# ext_proto_M.net
KiCad netlist of a schematic drawn in EAGLE
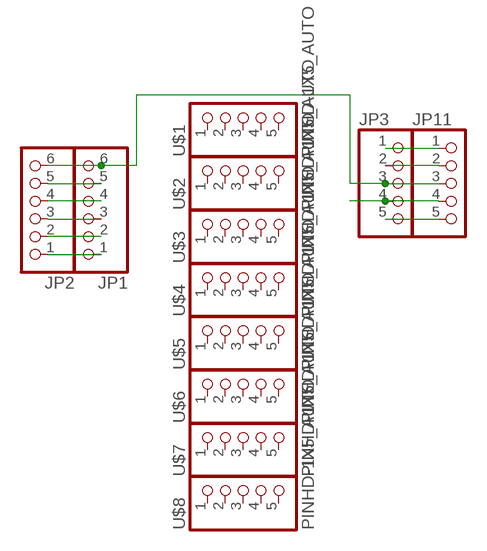
[diagram p0: schematic, sheet 1]

(export (version "E")
  (design (tool "Eeschema 10.0.6"))
  (components
    (comp (ref "JP1")
      (value "PINHD-1X6")
      (footprint "eagle-import:1X06")
      (libsource (lib "eagle-import") (part "PINHD-1X6"))
    )
    (comp (ref "JP2")
      (value "PINHD-1X6")
      (footprint "eagle-import:1X06")
      (libsource (lib "eagle-import") (part "PINHD-1X6"))
    )
    (comp (ref "JP3")
      (value "PINHD-1X5")
      (footprint "eagle-import:1X05")
      (libsource (lib "eagle-import") (part "PINHD-1X5"))
    )
    (comp (ref "JP11")
      (value "PINHD-1X5")
      (footprint "eagle-import:1X05")
      (libsource (lib "eagle-import") (part "PINHD-1X5"))
    )
    (comp (ref "U$1")
      (value "PINHD-1X5_AUTO")
      (footprint "eagle-import:1X5_AUTO")
      (libsource (lib "eagle-import") (part "PINHD-1X5_AUTO"))
    )
    (comp (ref "U$2")
      (value "PINHD-1X5_AUTO")
      (footprint "eagle-import:1X5_AUTO")
      (libsource (lib "eagle-import") (part "PINHD-1X5_AUTO"))
    )
    (comp (ref "U$3")
      (value "PINHD-1X5_AUTO")
      (footprint "eagle-import:1X5_AUTO")
      (libsource (lib "eagle-import") (part "PINHD-1X5_AUTO"))
    )
    (comp (ref "U$4")
      (value "PINHD-1X5_AUTO")
      (footprint "eagle-import:1X5_AUTO")
      (libsource (lib "eagle-import") (part "PINHD-1X5_AUTO"))
    )
    (comp (ref "U$5")
      (value "PINHD-1X5_AUTO")
      (footprint "eagle-import:1X5_AUTO")
      (libsource (lib "eagle-import") (part "PINHD-1X5_AUTO"))
    )
    (comp (ref "U$6")
      (value "PINHD-1X5_AUTO")
      (footprint "eagle-import:1X5_AUTO")
      (libsource (lib "eagle-import") (part "PINHD-1X5_AUTO"))
    )
    (comp (ref "U$7")
      (value "PINHD-1X5_AUTO")
      (footprint "eagle-import:1X5_AUTO")
      (libsource (lib "eagle-import") (part "PINHD-1X5_AUTO"))
    )
    (comp (ref "U$8")
      (value "PINHD-1X5_AUTO")
      (footprint "eagle-import:1X5_AUTO")
      (libsource (lib "eagle-import") (part "PINHD-1X5_AUTO"))
    )
  )
  (nets
    (net (code "1") (name "Net-(JP1-Pad1)") (class "Default")
      (node (ref "JP1") (pin "1") (pinfunction "1_1") (pintype "passive"))
      (node (ref "JP2") (pin "1") (pinfunction "1_1") (pintype "passive"))
    )
    (net (code "2") (name "Net-(JP1-Pad2)") (class "Default")
      (node (ref "JP1") (pin "2") (pinfunction "2_2") (pintype "passive"))
      (node (ref "JP2") (pin "2") (pinfunction "2_2") (pintype "passive"))
    )
    (net (code "3") (name "Net-(JP1-Pad3)") (class "Default")
      (node (ref "JP1") (pin "3") (pinfunction "3_3") (pintype "passive"))
      (node (ref "JP2") (pin "3") (pinfunction "3_3") (pintype "passive"))
    )
    (net (code "4") (name "Net-(JP1-Pad4)") (class "Default")
      (node (ref "JP1") (pin "4") (pinfunction "4_4") (pintype "passive"))
      (node (ref "JP2") (pin "4") (pinfunction "4_4") (pintype "passive"))
    )
    (net (code "5") (name "Net-(JP1-Pad5)") (class "Default")
      (node (ref "JP1") (pin "5") (pinfunction "5_5") (pintype "passive"))
      (node (ref "JP2") (pin "5") (pinfunction "5_5") (pintype "passive"))
    )
    (net (code "6") (name "Net-(JP1-Pad6)") (class "Default")
      (node (ref "JP1") (pin "6") (pinfunction "6_6") (pintype "passive"))
      (node (ref "JP11") (pin "3") (pinfunction "3_3") (pintype "passive"))
      (node (ref "JP2") (pin "6") (pinfunction "6_6") (pintype "passive"))
      (node (ref "JP3") (pin "3") (pinfunction "3_3") (pintype "passive"))
    )
    (net (code "7") (name "Net-(JP11-Pad1)") (class "Default")
      (node (ref "JP11") (pin "1") (pinfunction "1_1") (pintype "passive"))
      (node (ref "JP3") (pin "1") (pinfunction "1_1") (pintype "passive"))
    )
    (net (code "8") (name "Net-(JP11-Pad2)") (class "Default")
      (node (ref "JP11") (pin "2") (pinfunction "2_2") (pintype "passive"))
      (node (ref "JP3") (pin "2") (pinfunction "2_2") (pintype "passive"))
    )
    (net (code "9") (name "Net-(JP11-Pad4)") (class "Default")
      (node (ref "JP11") (pin "4") (pinfunction "4_4") (pintype "passive"))
      (node (ref "JP3") (pin "4") (pinfunction "4_4") (pintype "passive"))
    )
    (net (code "10") (name "Net-(JP11-Pad5)") (class "Default")
      (node (ref "JP11") (pin "5") (pinfunction "5_5") (pintype "passive"))
      (node (ref "JP3") (pin "5") (pinfunction "5_5") (pintype "passive"))
    )
    (net (code "11") (name "unconnected-(U$1-Pad1)") (class "Default")
      (node (ref "U$1") (pin "1") (pinfunction "1_1") (pintype "passive"))
    )
    (net (code "12") (name "unconnected-(U$1-Pad2)") (class "Default")
      (node (ref "U$1") (pin "2") (pinfunction "2_2") (pintype "passive"))
    )
    (net (code "13") (name "unconnected-(U$1-Pad3)") (class "Default")
      (node (ref "U$1") (pin "3") (pinfunction "3_3") (pintype "passive"))
    )
    (net (code "14") (name "unconnected-(U$1-Pad4)") (class "Default")
      (node (ref "U$1") (pin "4") (pinfunction "4_4") (pintype "passive"))
    )
    (net (code "15") (name "unconnected-(U$1-Pad5)") (class "Default")
      (node (ref "U$1") (pin "5") (pinfunction "5_5") (pintype "passive"))
    )
    (net (code "16") (name "unconnected-(U$2-Pad1)") (class "Default")
      (node (ref "U$2") (pin "1") (pinfunction "1_1") (pintype "passive"))
    )
    (net (code "17") (name "unconnected-(U$2-Pad2)") (class "Default")
      (node (ref "U$2") (pin "2") (pinfunction "2_2") (pintype "passive"))
    )
    (net (code "18") (name "unconnected-(U$2-Pad3)") (class "Default")
      (node (ref "U$2") (pin "3") (pinfunction "3_3") (pintype "passive"))
    )
    (net (code "19") (name "unconnected-(U$2-Pad4)") (class "Default")
      (node (ref "U$2") (pin "4") (pinfunction "4_4") (pintype "passive"))
    )
    (net (code "20") (name "unconnected-(U$2-Pad5)") (class "Default")
      (node (ref "U$2") (pin "5") (pinfunction "5_5") (pintype "passive"))
    )
    (net (code "21") (name "unconnected-(U$3-Pad1)") (class "Default")
      (node (ref "U$3") (pin "1") (pinfunction "1_1") (pintype "passive"))
    )
    (net (code "22") (name "unconnected-(U$3-Pad2)") (class "Default")
      (node (ref "U$3") (pin "2") (pinfunction "2_2") (pintype "passive"))
    )
    (net (code "23") (name "unconnected-(U$3-Pad3)") (class "Default")
      (node (ref "U$3") (pin "3") (pinfunction "3_3") (pintype "passive"))
    )
    (net (code "24") (name "unconnected-(U$3-Pad4)") (class "Default")
      (node (ref "U$3") (pin "4") (pinfunction "4_4") (pintype "passive"))
    )
    (net (code "25") (name "unconnected-(U$3-Pad5)") (class "Default")
      (node (ref "U$3") (pin "5") (pinfunction "5_5") (pintype "passive"))
    )
    (net (code "26") (name "unconnected-(U$4-Pad1)") (class "Default")
      (node (ref "U$4") (pin "1") (pinfunction "1_1") (pintype "passive"))
    )
    (net (code "27") (name "unconnected-(U$4-Pad2)") (class "Default")
      (node (ref "U$4") (pin "2") (pinfunction "2_2") (pintype "passive"))
    )
    (net (code "28") (name "unconnected-(U$4-Pad3)") (class "Default")
      (node (ref "U$4") (pin "3") (pinfunction "3_3") (pintype "passive"))
    )
    (net (code "29") (name "unconnected-(U$4-Pad4)") (class "Default")
      (node (ref "U$4") (pin "4") (pinfunction "4_4") (pintype "passive"))
    )
    (net (code "30") (name "unconnected-(U$4-Pad5)") (class "Default")
      (node (ref "U$4") (pin "5") (pinfunction "5_5") (pintype "passive"))
    )
    (net (code "31") (name "unconnected-(U$5-Pad1)") (class "Default")
      (node (ref "U$5") (pin "1") (pinfunction "1_1") (pintype "passive"))
    )
    (net (code "32") (name "unconnected-(U$5-Pad2)") (class "Default")
      (node (ref "U$5") (pin "2") (pinfunction "2_2") (pintype "passive"))
    )
    (net (code "33") (name "unconnected-(U$5-Pad3)") (class "Default")
      (node (ref "U$5") (pin "3") (pinfunction "3_3") (pintype "passive"))
    )
    (net (code "34") (name "unconnected-(U$5-Pad4)") (class "Default")
      (node (ref "U$5") (pin "4") (pinfunction "4_4") (pintype "passive"))
    )
    (net (code "35") (name "unconnected-(U$5-Pad5)") (class "Default")
      (node (ref "U$5") (pin "5") (pinfunction "5_5") (pintype "passive"))
    )
    (net (code "36") (name "unconnected-(U$6-Pad1)") (class "Default")
      (node (ref "U$6") (pin "1") (pinfunction "1_1") (pintype "passive"))
    )
    (net (code "37") (name "unconnected-(U$6-Pad2)") (class "Default")
      (node (ref "U$6") (pin "2") (pinfunction "2_2") (pintype "passive"))
    )
    (net (code "38") (name "unconnected-(U$6-Pad3)") (class "Default")
      (node (ref "U$6") (pin "3") (pinfunction "3_3") (pintype "passive"))
    )
    (net (code "39") (name "unconnected-(U$6-Pad4)") (class "Default")
      (node (ref "U$6") (pin "4") (pinfunction "4_4") (pintype "passive"))
    )
    (net (code "40") (name "unconnected-(U$6-Pad5)") (class "Default")
      (node (ref "U$6") (pin "5") (pinfunction "5_5") (pintype "passive"))
    )
    (net (code "41") (name "unconnected-(U$7-Pad1)") (class "Default")
      (node (ref "U$7") (pin "1") (pinfunction "1_1") (pintype "passive"))
    )
    (net (code "42") (name "unconnected-(U$7-Pad2)") (class "Default")
      (node (ref "U$7") (pin "2") (pinfunction "2_2") (pintype "passive"))
    )
    (net (code "43") (name "unconnected-(U$7-Pad3)") (class "Default")
      (node (ref "U$7") (pin "3") (pinfunction "3_3") (pintype "passive"))
    )
    (net (code "44") (name "unconnected-(U$7-Pad4)") (class "Default")
      (node (ref "U$7") (pin "4") (pinfunction "4_4") (pintype "passive"))
    )
    (net (code "45") (name "unconnected-(U$7-Pad5)") (class "Default")
      (node (ref "U$7") (pin "5") (pinfunction "5_5") (pintype "passive"))
    )
    (net (code "46") (name "unconnected-(U$8-Pad1)") (class "Default")
      (node (ref "U$8") (pin "1") (pinfunction "1_1") (pintype "passive"))
    )
    (net (code "47") (name "unconnected-(U$8-Pad2)") (class "Default")
      (node (ref "U$8") (pin "2") (pinfunction "2_2") (pintype "passive"))
    )
    (net (code "48") (name "unconnected-(U$8-Pad3)") (class "Default")
      (node (ref "U$8") (pin "3") (pinfunction "3_3") (pintype "passive"))
    )
    (net (code "49") (name "unconnected-(U$8-Pad4)") (class "Default")
      (node (ref "U$8") (pin "4") (pinfunction "4_4") (pintype "passive"))
    )
    (net (code "50") (name "unconnected-(U$8-Pad5)") (class "Default")
      (node (ref "U$8") (pin "5") (pinfunction "5_5") (pintype "passive"))
    )
  )
)
